# LCD_Direct.net
KiCad netlist of a schematic drawn in Altium Designer
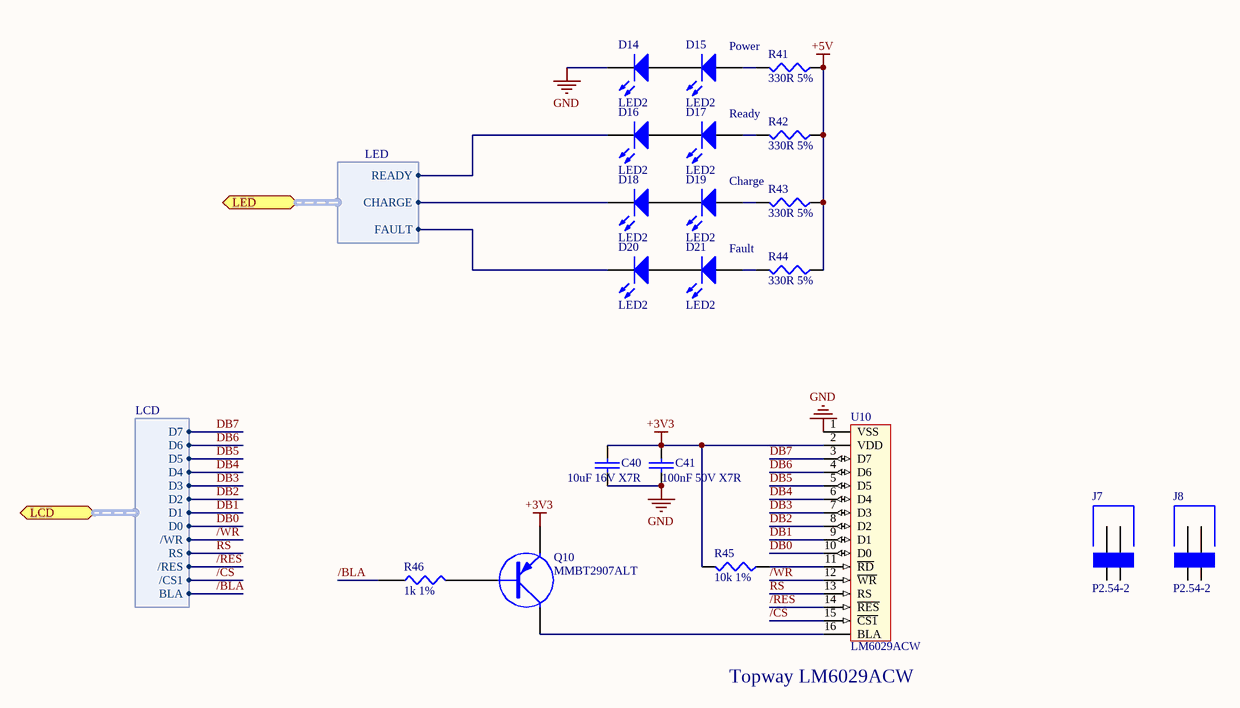
[diagram p0: LCD_Direct.SchDoc]

(export (version "E")
  (design (tool "Eeschema 10.0.6"))
  (components
    (comp (ref "C40")
      (value "10uF 16V X7R")
      (footprint "IPC-7352 Chip_Capacitor_N:CAPC3216N")
      (libsource (lib "") (part "CAP_1"))
    )
    (comp (ref "C41")
      (value "100nF 50V X7R")
      (footprint "IPC-7352 Chip_Capacitor_N:CAPC2012N")
      (description "Capacitor")
      (libsource (lib "*") (part "CAP"))
    )
    (comp (ref "D14")
      (value "LED2")
      (footprint "3.2X1.6X1.1")
      (description "Typical RED, GREEN, YELLOW, AMBER GaAs LED")
      (fields (field (name "PUBLISHER") "Altium Limited"))
      (libsource (lib "Miscellaneous Devices") (part "LED2"))
    )
    (comp (ref "D15")
      (value "LED2")
      (footprint "3.2X1.6X1.1")
      (description "Typical RED, GREEN, YELLOW, AMBER GaAs LED")
      (fields (field (name "PUBLISHER") "Altium Limited"))
      (libsource (lib "Miscellaneous Devices") (part "LED2"))
    )
    (comp (ref "D16")
      (value "LED2")
      (footprint "3.2X1.6X1.1")
      (description "Typical RED, GREEN, YELLOW, AMBER GaAs LED")
      (fields (field (name "PUBLISHER") "Altium Limited"))
      (libsource (lib "Miscellaneous Devices") (part "LED2"))
    )
    (comp (ref "D17")
      (value "LED2")
      (footprint "3.2X1.6X1.1")
      (description "Typical RED, GREEN, YELLOW, AMBER GaAs LED")
      (fields (field (name "PUBLISHER") "Altium Limited"))
      (libsource (lib "Miscellaneous Devices") (part "LED2"))
    )
    (comp (ref "D18")
      (value "LED2")
      (footprint "3.2X1.6X1.1")
      (description "Typical RED, GREEN, YELLOW, AMBER GaAs LED")
      (fields (field (name "PUBLISHER") "Altium Limited"))
      (libsource (lib "Miscellaneous Devices") (part "LED2"))
    )
    (comp (ref "D19")
      (value "LED2")
      (footprint "3.2X1.6X1.1")
      (description "Typical RED, GREEN, YELLOW, AMBER GaAs LED")
      (fields (field (name "PUBLISHER") "Altium Limited"))
      (libsource (lib "Miscellaneous Devices") (part "LED2"))
    )
    (comp (ref "D20")
      (value "LED2")
      (footprint "3.2X1.6X1.1")
      (description "Typical RED, GREEN, YELLOW, AMBER GaAs LED")
      (fields (field (name "PUBLISHER") "Altium Limited"))
      (libsource (lib "Miscellaneous Devices") (part "LED2"))
    )
    (comp (ref "D21")
      (value "LED2")
      (footprint "3.2X1.6X1.1")
      (description "Typical RED, GREEN, YELLOW, AMBER GaAs LED")
      (fields (field (name "PUBLISHER") "Altium Limited"))
      (libsource (lib "Miscellaneous Devices") (part "LED2"))
    )
    (comp (ref "J7")
      (value "P2.54-2")
      (footprint "UserPcbLib:JP2-P2.54")
      (libsource (lib "UserSchlib") (part "JP2-2.54"))
    )
    (comp (ref "J8")
      (value "P2.54-2")
      (footprint "UserPcbLib:JP2-P2.54")
      (libsource (lib "UserSchlib") (part "JP2-2.54"))
    )
    (comp (ref "Q10")
      (value "MMBT2907ALT")
      (footprint "SOT23_N:SOT23-3N")
      (description "PNP transitor")
      (libsource (lib "*") (part "MMBT3906"))
    )
    (comp (ref "R41")
      (value "330R 5%")
      (footprint "IPC-7352 Chip_Resistor_N:RESC2012N")
      (description "Resistor")
      (libsource (lib "Miscellaneous Devices") (part "Res3"))
    )
    (comp (ref "R42")
      (value "330R 5%")
      (footprint "IPC-7352 Chip_Resistor_N:RESC2012N")
      (description "Resistor")
      (libsource (lib "Miscellaneous Devices") (part "Res3"))
    )
    (comp (ref "R43")
      (value "330R 5%")
      (footprint "IPC-7352 Chip_Resistor_N:RESC2012N")
      (description "Resistor")
      (libsource (lib "Miscellaneous Devices") (part "Res3"))
    )
    (comp (ref "R44")
      (value "330R 5%")
      (footprint "IPC-7352 Chip_Resistor_N:RESC2012N")
      (description "Resistor")
      (libsource (lib "Miscellaneous Devices") (part "Res3"))
    )
    (comp (ref "R45")
      (value "10k 1%")
      (footprint "IPC-7352 Chip_Resistor_N:RESC2012N")
      (description "Resistor")
      (fields (field (name "PUBLISHER") "Altium Limited"))
      (libsource (lib "Miscellaneous Devices") (part "Res3"))
    )
    (comp (ref "R46")
      (value "1k 1%")
      (footprint "IPC-7352 Chip_Resistor_N:RESC2012N")
      (libsource (lib "*") (part "RES1"))
    )
    (comp (ref "U10")
      (value "LM6029ACW")
      (footprint "UserPcbLib:LM6029A")
      (description "Topway LCD module 3.3V")
      (libsource (lib "UserSchlib") (part "LM6029A"))
    )
  )
  (nets
    (net (code "3") (name "+3V3") (class "Default")
      (node (ref "C40") (pin "1") (pintype "passive"))
      (node (ref "C41") (pin "1") (pinfunction "1_1") (pintype "passive"))
      (node (ref "Q10") (pin "2") (pinfunction "E_2") (pintype "passive"))
      (node (ref "R45") (pin "2") (pinfunction "2_2") (pintype "passive"))
      (node (ref "U10") (pin "2") (pinfunction "VDD_2") (pintype "power_in"))
    )
    (net (code "4") (name "+5V") (class "Default")
      (node (ref "R41") (pin "1") (pinfunction "1_1") (pintype "passive"))
      (node (ref "R42") (pin "1") (pinfunction "1_1") (pintype "passive"))
      (node (ref "R43") (pin "1") (pinfunction "1_1") (pintype "passive"))
      (node (ref "R44") (pin "1") (pinfunction "1_1") (pintype "passive"))
    )
    (net (code "5") (name "/CHARGE") (class "Default")
      (node (ref "D18") (pin "2") (pinfunction "K_2") (pintype "passive"))
    )
    (net (code "6") (name "/DB0") (class "Default")
      (node (ref "U10") (pin "10") (pinfunction "D0_10") (pintype "bidirectional"))
    )
    (net (code "7") (name "/DB1") (class "Default")
      (node (ref "U10") (pin "9") (pinfunction "D1_9") (pintype "bidirectional"))
    )
    (net (code "8") (name "/DB2") (class "Default")
      (node (ref "U10") (pin "8") (pinfunction "D2_8") (pintype "bidirectional"))
    )
    (net (code "9") (name "/DB3") (class "Default")
      (node (ref "U10") (pin "7") (pinfunction "D3_7") (pintype "bidirectional"))
    )
    (net (code "10") (name "/DB4") (class "Default")
      (node (ref "U10") (pin "6") (pinfunction "D4_6") (pintype "bidirectional"))
    )
    (net (code "11") (name "/DB5") (class "Default")
      (node (ref "U10") (pin "5") (pinfunction "D5_5") (pintype "bidirectional"))
    )
    (net (code "12") (name "/DB6") (class "Default")
      (node (ref "U10") (pin "4") (pinfunction "D6_4") (pintype "bidirectional"))
    )
    (net (code "13") (name "/DB7") (class "Default")
      (node (ref "U10") (pin "3") (pinfunction "D7_3") (pintype "bidirectional"))
    )
    (net (code "14") (name "/FAULT") (class "Default")
      (node (ref "D20") (pin "2") (pinfunction "K_2") (pintype "passive"))
    )
    (net (code "15") (name "/READY") (class "Default")
      (node (ref "D16") (pin "2") (pinfunction "K_2") (pintype "passive"))
    )
    (net (code "16") (name "/RS") (class "Default")
      (node (ref "U10") (pin "13") (pinfunction "RS_13") (pintype "input"))
    )
    (net (code "19") (name "/{slash}BLA") (class "Default")
      (node (ref "R46") (pin "1") (pinfunction "1_1") (pintype "passive"))
    )
    (net (code "20") (name "/{slash}CS") (class "Default")
      (node (ref "U10") (pin "15") (pinfunction "CS1_15") (pintype "input"))
    )
    (net (code "21") (name "/{slash}RES") (class "Default")
      (node (ref "U10") (pin "14") (pinfunction "RES_14") (pintype "input"))
    )
    (net (code "22") (name "/{slash}WR") (class "Default")
      (node (ref "U10") (pin "12") (pinfunction "WR_12") (pintype "input"))
    )
    (net (code "23") (name "GND") (class "Default")
      (node (ref "C40") (pin "2") (pintype "passive"))
      (node (ref "C41") (pin "2") (pinfunction "2_2") (pintype "passive"))
      (node (ref "D14") (pin "2") (pinfunction "K_2") (pintype "passive"))
      (node (ref "U10") (pin "1") (pinfunction "VSS_1") (pintype "power_in"))
    )
    (net (code "24") (name "Net-(D14-A)") (class "Default")
      (node (ref "D14") (pin "1") (pinfunction "A_1") (pintype "passive"))
      (node (ref "D15") (pin "2") (pinfunction "K_2") (pintype "passive"))
    )
    (net (code "25") (name "Net-(D15-A)") (class "Default")
      (node (ref "D15") (pin "1") (pinfunction "A_1") (pintype "passive"))
      (node (ref "R41") (pin "2") (pinfunction "2_2") (pintype "passive"))
    )
    (net (code "26") (name "Net-(D16-A)") (class "Default")
      (node (ref "D16") (pin "1") (pinfunction "A_1") (pintype "passive"))
      (node (ref "D17") (pin "2") (pinfunction "K_2") (pintype "passive"))
    )
    (net (code "27") (name "Net-(D17-A)") (class "Default")
      (node (ref "D17") (pin "1") (pinfunction "A_1") (pintype "passive"))
      (node (ref "R42") (pin "2") (pinfunction "2_2") (pintype "passive"))
    )
    (net (code "28") (name "Net-(D18-A)") (class "Default")
      (node (ref "D18") (pin "1") (pinfunction "A_1") (pintype "passive"))
      (node (ref "D19") (pin "2") (pinfunction "K_2") (pintype "passive"))
    )
    (net (code "29") (name "Net-(D19-A)") (class "Default")
      (node (ref "D19") (pin "1") (pinfunction "A_1") (pintype "passive"))
      (node (ref "R43") (pin "2") (pinfunction "2_2") (pintype "passive"))
    )
    (net (code "30") (name "Net-(D20-A)") (class "Default")
      (node (ref "D20") (pin "1") (pinfunction "A_1") (pintype "passive"))
      (node (ref "D21") (pin "2") (pinfunction "K_2") (pintype "passive"))
    )
    (net (code "31") (name "Net-(D21-A)") (class "Default")
      (node (ref "D21") (pin "1") (pinfunction "A_1") (pintype "passive"))
      (node (ref "R44") (pin "2") (pinfunction "2_2") (pintype "passive"))
    )
    (net (code "32") (name "Net-(Q10-B)") (class "Default")
      (node (ref "Q10") (pin "1") (pinfunction "B_1") (pintype "passive"))
      (node (ref "R46") (pin "2") (pinfunction "2_2") (pintype "passive"))
    )
    (net (code "33") (name "Net-(Q10-C)") (class "Default")
      (node (ref "Q10") (pin "3") (pinfunction "C_3") (pintype "passive"))
      (node (ref "U10") (pin "16") (pinfunction "BLA_16") (pintype "power_in"))
    )
    (net (code "34") (name "Net-(U10-RD)") (class "Default")
      (node (ref "R45") (pin "1") (pinfunction "1_1") (pintype "passive"))
      (node (ref "U10") (pin "11") (pinfunction "RD_11") (pintype "input"))
    )
    (net (code "35") (name "unconnected-(J7-Pad1)") (class "Default")
      (node (ref "J7") (pin "1") (pinfunction "1_1") (pintype "power_in"))
    )
    (net (code "36") (name "unconnected-(J7-Pad2)") (class "Default")
      (node (ref "J7") (pin "2") (pinfunction "2_2") (pintype "power_in"))
    )
    (net (code "37") (name "unconnected-(J8-Pad1)") (class "Default")
      (node (ref "J8") (pin "1") (pinfunction "1_1") (pintype "power_in"))
    )
    (net (code "38") (name "unconnected-(J8-Pad2)") (class "Default")
      (node (ref "J8") (pin "2") (pinfunction "2_2") (pintype "power_in"))
    )
  )
)
